# power.net
KiCad netlist of a schematic drawn in Altium Designer
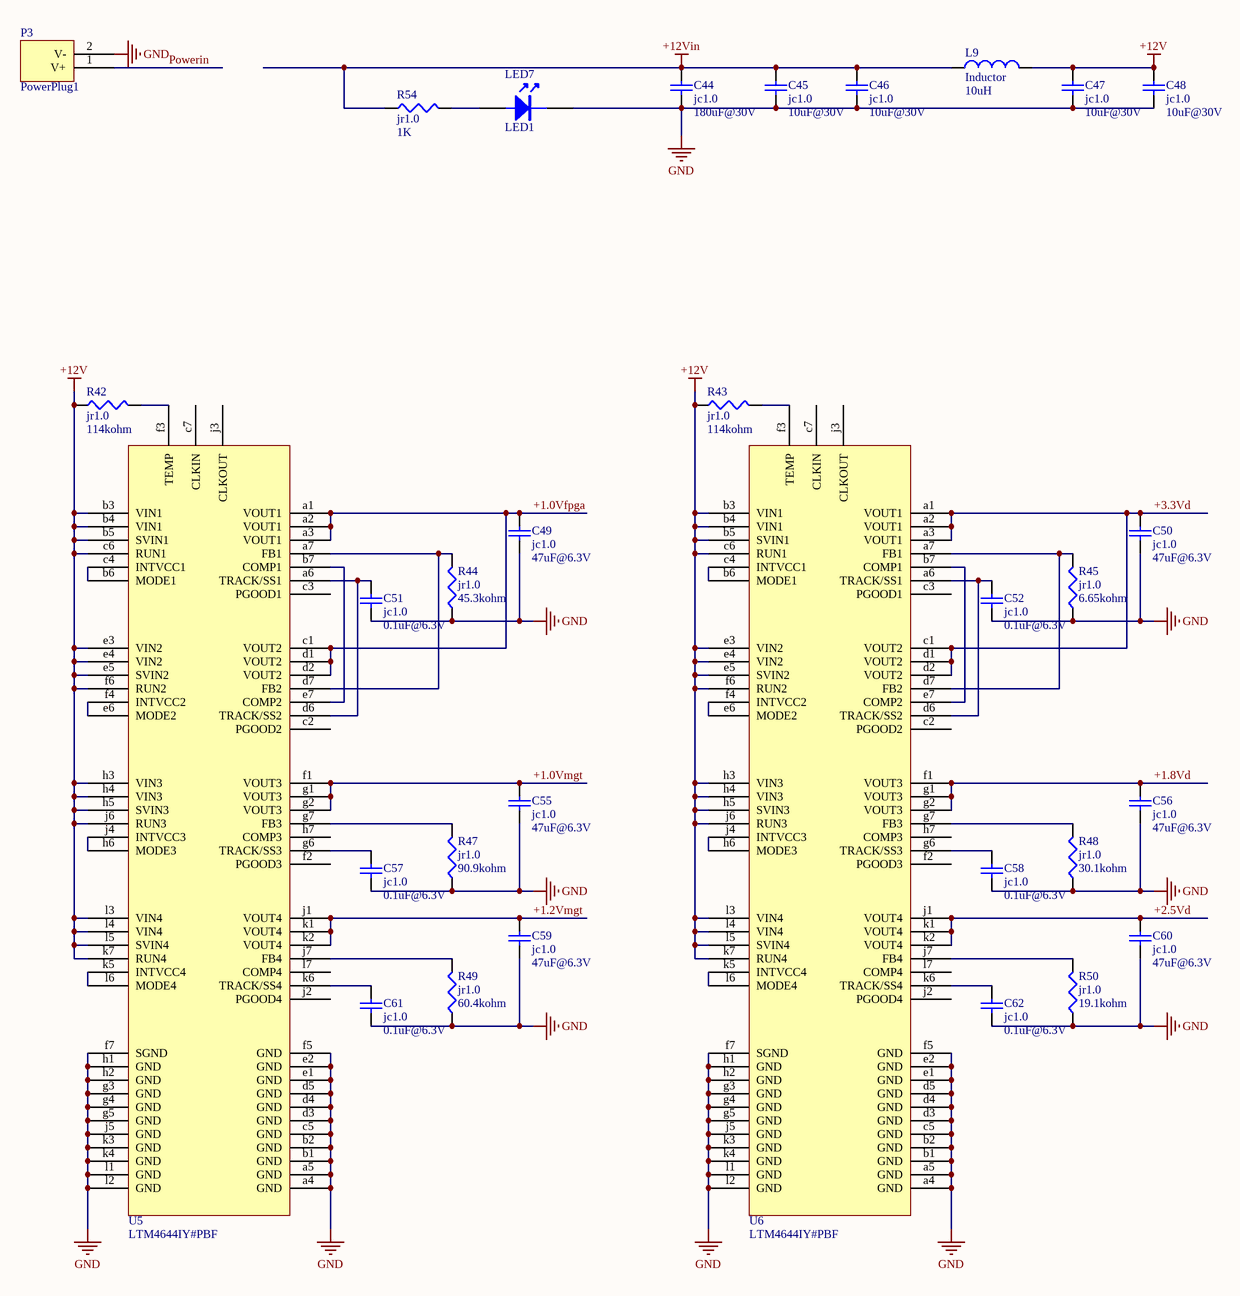
[diagram p0: power.SchDoc]

(export (version "E")
  (design (tool "Eeschema 10.0.6"))
  (components
    (comp (ref "C44")
      (value "jc1.0")
      (footprint "2220")
      (description "Capacitor")
      (fields (field (name "ALTIUM_VALUE") "180uF@30V") (field (name "PUBLISHER") "Altium Limited"))
      (libsource (lib "LIB01DXP2006SchLib") (part "Cap"))
    )
    (comp (ref "C45")
      (value "jc1.0")
      (footprint "2220")
      (description "Capacitor")
      (fields (field (name "ALTIUM_VALUE") "10uF@30V") (field (name "PUBLISHER") "Altium Limited"))
      (libsource (lib "LIB01DXP2006SchLib") (part "Cap"))
    )
    (comp (ref "C46")
      (value "jc1.0")
      (footprint "2220")
      (description "Capacitor")
      (fields (field (name "ALTIUM_VALUE") "10uF@30V") (field (name "PUBLISHER") "Altium Limited"))
      (libsource (lib "LIB01DXP2006SchLib") (part "Cap"))
    )
    (comp (ref "C47")
      (value "jc1.0")
      (footprint "2220")
      (description "Capacitor")
      (fields (field (name "ALTIUM_VALUE") "10uF@30V") (field (name "PUBLISHER") "Altium Limited"))
      (libsource (lib "LIB01DXP2006SchLib") (part "Cap"))
    )
    (comp (ref "C48")
      (value "jc1.0")
      (footprint "2220")
      (description "Capacitor")
      (fields (field (name "ALTIUM_VALUE") "10uF@30V") (field (name "PUBLISHER") "Altium Limited"))
      (libsource (lib "LIB01DXP2006SchLib") (part "Cap"))
    )
    (comp (ref "C49")
      (value "jc1.0")
      (footprint "0805")
      (description "Capacitor")
      (fields (field (name "ALTIUM_VALUE") "47uF@6.3V") (field (name "PUBLISHER") "Altium Limited"))
      (libsource (lib "LIB01DXP2006SchLib") (part "Cap"))
    )
    (comp (ref "C50")
      (value "jc1.0")
      (footprint "0805")
      (description "Capacitor")
      (fields (field (name "ALTIUM_VALUE") "47uF@6.3V") (field (name "PUBLISHER") "Altium Limited"))
      (libsource (lib "LIB01DXP2006SchLib") (part "Cap"))
    )
    (comp (ref "C51")
      (value "jc1.0")
      (footprint "0402")
      (description "Capacitor")
      (fields (field (name "ALTIUM_VALUE") "0.1uF@6.3V") (field (name "PUBLISHER") "Altium Limited"))
      (libsource (lib "LIB01DXP2006SchLib") (part "Cap"))
    )
    (comp (ref "C52")
      (value "jc1.0")
      (footprint "0402")
      (description "Capacitor")
      (fields (field (name "ALTIUM_VALUE") "0.1uF@6.3V") (field (name "PUBLISHER") "Altium Limited"))
      (libsource (lib "LIB01DXP2006SchLib") (part "Cap"))
    )
    (comp (ref "C55")
      (value "jc1.0")
      (footprint "0805")
      (description "Capacitor")
      (fields (field (name "ALTIUM_VALUE") "47uF@6.3V") (field (name "PUBLISHER") "Altium Limited"))
      (libsource (lib "LIB01DXP2006SchLib") (part "Cap"))
    )
    (comp (ref "C56")
      (value "jc1.0")
      (footprint "0805")
      (description "Capacitor")
      (fields (field (name "ALTIUM_VALUE") "47uF@6.3V") (field (name "PUBLISHER") "Altium Limited"))
      (libsource (lib "LIB01DXP2006SchLib") (part "Cap"))
    )
    (comp (ref "C57")
      (value "jc1.0")
      (footprint "0402")
      (description "Capacitor")
      (fields (field (name "ALTIUM_VALUE") "0.1uF@6.3V") (field (name "PUBLISHER") "Altium Limited"))
      (libsource (lib "LIB01DXP2006SchLib") (part "Cap"))
    )
    (comp (ref "C58")
      (value "jc1.0")
      (footprint "0402")
      (description "Capacitor")
      (fields (field (name "ALTIUM_VALUE") "0.1uF@6.3V") (field (name "PUBLISHER") "Altium Limited"))
      (libsource (lib "LIB01DXP2006SchLib") (part "Cap"))
    )
    (comp (ref "C59")
      (value "jc1.0")
      (footprint "0805")
      (description "Capacitor")
      (fields (field (name "ALTIUM_VALUE") "47uF@6.3V") (field (name "PUBLISHER") "Altium Limited"))
      (libsource (lib "LIB01DXP2006SchLib") (part "Cap"))
    )
    (comp (ref "C60")
      (value "jc1.0")
      (footprint "0805")
      (description "Capacitor")
      (fields (field (name "ALTIUM_VALUE") "47uF@6.3V") (field (name "PUBLISHER") "Altium Limited"))
      (libsource (lib "LIB01DXP2006SchLib") (part "Cap"))
    )
    (comp (ref "C61")
      (value "jc1.0")
      (footprint "0402")
      (description "Capacitor")
      (fields (field (name "ALTIUM_VALUE") "0.1uF@6.3V") (field (name "PUBLISHER") "Altium Limited"))
      (libsource (lib "LIB01DXP2006SchLib") (part "Cap"))
    )
    (comp (ref "C62")
      (value "jc1.0")
      (footprint "0402")
      (description "Capacitor")
      (fields (field (name "ALTIUM_VALUE") "0.1uF@6.3V") (field (name "PUBLISHER") "Altium Limited"))
      (libsource (lib "LIB01DXP2006SchLib") (part "Cap"))
    )
    (comp (ref "L9")
      (value "Inductor")
      (footprint "AXIAL0.3 - 35")
      (fields (field (name "ALTIUM_VALUE") "10uH") (field (name "PUBLISHER") "Altium Limited"))
      (libsource (lib "LIB01DXP2006SchLib") (part "Inductor"))
    )
    (comp (ref "LED7") (value "LED1") (footprint "LED1") (libsource (lib "LIB01DXP2006SchLib") (part "LED1")))
    (comp (ref "P3")
      (value "PowerPlug1")
      (footprint "POWERPLUG1")
      (libsource (lib "LIB01DXP2006SchLib") (part "PowerPlug1"))
    )
    (comp (ref "R42")
      (value "jr1.0")
      (footprint "0402")
      (description "Resistor")
      (fields (field (name "ALTIUM_VALUE") "114kohm") (field (name "PUBLISHER") "Altium Limited"))
      (libsource (lib "LIB01DXP2006SchLib") (part "Res"))
    )
    (comp (ref "R43")
      (value "jr1.0")
      (footprint "0402")
      (description "Resistor")
      (fields (field (name "ALTIUM_VALUE") "114kohm") (field (name "PUBLISHER") "Altium Limited"))
      (libsource (lib "LIB01DXP2006SchLib") (part "Res"))
    )
    (comp (ref "R44")
      (value "jr1.0")
      (footprint "0805")
      (description "Resistor")
      (fields (field (name "ALTIUM_VALUE") "45.3kohm") (field (name "PUBLISHER") "Altium Limited"))
      (libsource (lib "LIB01DXP2006SchLib") (part "Res"))
    )
    (comp (ref "R45")
      (value "jr1.0")
      (footprint "0805")
      (description "Resistor")
      (fields (field (name "ALTIUM_VALUE") "6.65kohm") (field (name "PUBLISHER") "Altium Limited"))
      (libsource (lib "LIB01DXP2006SchLib") (part "Res"))
    )
    (comp (ref "R47")
      (value "jr1.0")
      (footprint "0805")
      (description "Resistor")
      (fields (field (name "ALTIUM_VALUE") "90.9kohm") (field (name "PUBLISHER") "Altium Limited"))
      (libsource (lib "LIB01DXP2006SchLib") (part "Res"))
    )
    (comp (ref "R48")
      (value "jr1.0")
      (footprint "0805")
      (description "Resistor")
      (fields (field (name "ALTIUM_VALUE") "30.1kohm") (field (name "PUBLISHER") "Altium Limited"))
      (libsource (lib "LIB01DXP2006SchLib") (part "Res"))
    )
    (comp (ref "R49")
      (value "jr1.0")
      (footprint "0805")
      (description "Resistor")
      (fields (field (name "ALTIUM_VALUE") "60.4kohm") (field (name "PUBLISHER") "Altium Limited"))
      (libsource (lib "LIB01DXP2006SchLib") (part "Res"))
    )
    (comp (ref "R50")
      (value "jr1.0")
      (footprint "0805")
      (description "Resistor")
      (fields (field (name "ALTIUM_VALUE") "19.1kohm") (field (name "PUBLISHER") "Altium Limited"))
      (libsource (lib "LIB01DXP2006SchLib") (part "Res"))
    )
    (comp (ref "R54")
      (value "jr1.0")
      (footprint "0805")
      (description "Resistor")
      (fields (field (name "ALTIUM_VALUE") "1K") (field (name "PUBLISHER") "Altium Limited"))
      (libsource (lib "LIB01DXP2006SchLib") (part "Res"))
    )
    (comp (ref "U5")
      (value "LTM4644IY#PBF")
      (footprint "BGA77C127P7X11_900X1500X521")
      (libsource (lib "LIB01DXP2006SchLib") (part "LTM4644IY#PBF"))
    )
    (comp (ref "U6")
      (value "LTM4644IY#PBF")
      (footprint "BGA77C127P7X11_900X1500X521")
      (libsource (lib "LIB01DXP2006SchLib") (part "LTM4644IY#PBF"))
    )
  )
  (nets
    (net (code "1") (name "+12V") (class "Default")
      (node (ref "C47") (pin "2") (pinfunction "2_2") (pintype "passive"))
      (node (ref "C48") (pin "2") (pinfunction "2_2") (pintype "passive"))
      (node (ref "L9") (pin "2") (pinfunction "2_2") (pintype "passive"))
      (node (ref "R42") (pin "1") (pinfunction "1_1") (pintype "passive"))
      (node (ref "R43") (pin "1") (pinfunction "1_1") (pintype "passive"))
      (node (ref "U5") (pin "b3") (pinfunction "VIN1_b3") (pintype "passive"))
      (node (ref "U5") (pin "b4") (pinfunction "VIN1_b4") (pintype "passive"))
      (node (ref "U5") (pin "b5") (pinfunction "SVIN1_b5") (pintype "passive"))
      (node (ref "U5") (pin "c6") (pinfunction "RUN1_c6") (pintype "passive"))
      (node (ref "U5") (pin "e3") (pinfunction "VIN2_e3") (pintype "passive"))
      (node (ref "U5") (pin "e4") (pinfunction "VIN2_e4") (pintype "passive"))
      (node (ref "U5") (pin "e5") (pinfunction "SVIN2_e5") (pintype "passive"))
      (node (ref "U5") (pin "f6") (pinfunction "RUN2_f6") (pintype "passive"))
      (node (ref "U5") (pin "h3") (pinfunction "VIN3_h3") (pintype "passive"))
      (node (ref "U5") (pin "h4") (pinfunction "VIN3_h4") (pintype "passive"))
      (node (ref "U5") (pin "h5") (pinfunction "SVIN3_h5") (pintype "passive"))
      (node (ref "U5") (pin "j6") (pinfunction "RUN3_j6") (pintype "passive"))
      (node (ref "U5") (pin "k7") (pinfunction "RUN4_k7") (pintype "passive"))
      (node (ref "U5") (pin "l3") (pinfunction "VIN4_l3") (pintype "passive"))
      (node (ref "U5") (pin "l4") (pinfunction "VIN4_l4") (pintype "passive"))
      (node (ref "U5") (pin "l5") (pinfunction "SVIN4_l5") (pintype "passive"))
      (node (ref "U6") (pin "b3") (pinfunction "VIN1_b3") (pintype "passive"))
      (node (ref "U6") (pin "b4") (pinfunction "VIN1_b4") (pintype "passive"))
      (node (ref "U6") (pin "b5") (pinfunction "SVIN1_b5") (pintype "passive"))
      (node (ref "U6") (pin "c6") (pinfunction "RUN1_c6") (pintype "passive"))
      (node (ref "U6") (pin "e3") (pinfunction "VIN2_e3") (pintype "passive"))
      (node (ref "U6") (pin "e4") (pinfunction "VIN2_e4") (pintype "passive"))
      (node (ref "U6") (pin "e5") (pinfunction "SVIN2_e5") (pintype "passive"))
      (node (ref "U6") (pin "f6") (pinfunction "RUN2_f6") (pintype "passive"))
      (node (ref "U6") (pin "h3") (pinfunction "VIN3_h3") (pintype "passive"))
      (node (ref "U6") (pin "h4") (pinfunction "VIN3_h4") (pintype "passive"))
      (node (ref "U6") (pin "h5") (pinfunction "SVIN3_h5") (pintype "passive"))
      (node (ref "U6") (pin "j6") (pinfunction "RUN3_j6") (pintype "passive"))
      (node (ref "U6") (pin "k7") (pinfunction "RUN4_k7") (pintype "passive"))
      (node (ref "U6") (pin "l3") (pinfunction "VIN4_l3") (pintype "passive"))
      (node (ref "U6") (pin "l4") (pinfunction "VIN4_l4") (pintype "passive"))
      (node (ref "U6") (pin "l5") (pinfunction "SVIN4_l5") (pintype "passive"))
    )
    (net (code "2") (name "+12Vin") (class "Default")
      (node (ref "C44") (pin "2") (pinfunction "2_2") (pintype "passive"))
      (node (ref "C45") (pin "2") (pinfunction "2_2") (pintype "passive"))
      (node (ref "C46") (pin "2") (pinfunction "2_2") (pintype "passive"))
      (node (ref "L9") (pin "1") (pinfunction "1_1") (pintype "passive"))
      (node (ref "R54") (pin "1") (pinfunction "1_1") (pintype "passive"))
    )
    (net (code "3") (name "/+1.0Vfpga") (class "Default")
      (node (ref "C49") (pin "2") (pinfunction "2_2") (pintype "passive"))
      (node (ref "U5") (pin "a1") (pinfunction "VOUT1_a1") (pintype "passive"))
      (node (ref "U5") (pin "a2") (pinfunction "VOUT1_a2") (pintype "passive"))
      (node (ref "U5") (pin "a3") (pinfunction "VOUT1_a3") (pintype "passive"))
      (node (ref "U5") (pin "c1") (pinfunction "VOUT2_c1") (pintype "passive"))
      (node (ref "U5") (pin "d1") (pinfunction "VOUT2_d1") (pintype "passive"))
      (node (ref "U5") (pin "d2") (pinfunction "VOUT2_d2") (pintype "passive"))
    )
    (net (code "4") (name "/+1.0Vmgt") (class "Default")
      (node (ref "C55") (pin "2") (pinfunction "2_2") (pintype "passive"))
      (node (ref "U5") (pin "f1") (pinfunction "VOUT3_f1") (pintype "passive"))
      (node (ref "U5") (pin "g1") (pinfunction "VOUT3_g1") (pintype "passive"))
      (node (ref "U5") (pin "g2") (pinfunction "VOUT3_g2") (pintype "passive"))
    )
    (net (code "5") (name "/+1.2Vmgt") (class "Default")
      (node (ref "C59") (pin "2") (pinfunction "2_2") (pintype "passive"))
      (node (ref "U5") (pin "j1") (pinfunction "VOUT4_j1") (pintype "passive"))
      (node (ref "U5") (pin "k1") (pinfunction "VOUT4_k1") (pintype "passive"))
      (node (ref "U5") (pin "k2") (pinfunction "VOUT4_k2") (pintype "passive"))
    )
    (net (code "6") (name "/+1.8Vd") (class "Default")
      (node (ref "C56") (pin "2") (pinfunction "2_2") (pintype "passive"))
      (node (ref "U6") (pin "f1") (pinfunction "VOUT3_f1") (pintype "passive"))
      (node (ref "U6") (pin "g1") (pinfunction "VOUT3_g1") (pintype "passive"))
      (node (ref "U6") (pin "g2") (pinfunction "VOUT3_g2") (pintype "passive"))
    )
    (net (code "7") (name "/+2.5Vd") (class "Default")
      (node (ref "C60") (pin "2") (pinfunction "2_2") (pintype "passive"))
      (node (ref "U6") (pin "j1") (pinfunction "VOUT4_j1") (pintype "passive"))
      (node (ref "U6") (pin "k1") (pinfunction "VOUT4_k1") (pintype "passive"))
      (node (ref "U6") (pin "k2") (pinfunction "VOUT4_k2") (pintype "passive"))
    )
    (net (code "8") (name "/+3.3Vd") (class "Default")
      (node (ref "C50") (pin "2") (pinfunction "2_2") (pintype "passive"))
      (node (ref "U6") (pin "a1") (pinfunction "VOUT1_a1") (pintype "passive"))
      (node (ref "U6") (pin "a2") (pinfunction "VOUT1_a2") (pintype "passive"))
      (node (ref "U6") (pin "a3") (pinfunction "VOUT1_a3") (pintype "passive"))
      (node (ref "U6") (pin "c1") (pinfunction "VOUT2_c1") (pintype "passive"))
      (node (ref "U6") (pin "d1") (pinfunction "VOUT2_d1") (pintype "passive"))
      (node (ref "U6") (pin "d2") (pinfunction "VOUT2_d2") (pintype "passive"))
    )
    (net (code "9") (name "/Powerin") (class "Default")
      (node (ref "P3") (pin "1") (pinfunction "V+_1") (pintype "passive"))
    )
    (net (code "10") (name "GND") (class "Default")
      (node (ref "C44") (pin "1") (pinfunction "1_1") (pintype "passive"))
      (node (ref "C45") (pin "1") (pinfunction "1_1") (pintype "passive"))
      (node (ref "C46") (pin "1") (pinfunction "1_1") (pintype "passive"))
      (node (ref "C47") (pin "1") (pinfunction "1_1") (pintype "passive"))
      (node (ref "C48") (pin "1") (pinfunction "1_1") (pintype "passive"))
      (node (ref "C49") (pin "1") (pinfunction "1_1") (pintype "passive"))
      (node (ref "C50") (pin "1") (pinfunction "1_1") (pintype "passive"))
      (node (ref "C51") (pin "1") (pinfunction "1_1") (pintype "passive"))
      (node (ref "C52") (pin "1") (pinfunction "1_1") (pintype "passive"))
      (node (ref "C55") (pin "1") (pinfunction "1_1") (pintype "passive"))
      (node (ref "C56") (pin "1") (pinfunction "1_1") (pintype "passive"))
      (node (ref "C57") (pin "1") (pinfunction "1_1") (pintype "passive"))
      (node (ref "C58") (pin "1") (pinfunction "1_1") (pintype "passive"))
      (node (ref "C59") (pin "1") (pinfunction "1_1") (pintype "passive"))
      (node (ref "C60") (pin "1") (pinfunction "1_1") (pintype "passive"))
      (node (ref "C61") (pin "1") (pinfunction "1_1") (pintype "passive"))
      (node (ref "C62") (pin "1") (pinfunction "1_1") (pintype "passive"))
      (node (ref "LED7") (pin "2") (pinfunction "2_2") (pintype "passive"))
      (node (ref "P3") (pin "2") (pinfunction "V-_2") (pintype "passive"))
      (node (ref "R44") (pin "1") (pinfunction "1_1") (pintype "passive"))
      (node (ref "R45") (pin "1") (pinfunction "1_1") (pintype "passive"))
      (node (ref "R47") (pin "1") (pinfunction "1_1") (pintype "passive"))
      (node (ref "R48") (pin "1") (pinfunction "1_1") (pintype "passive"))
      (node (ref "R49") (pin "1") (pinfunction "1_1") (pintype "passive"))
      (node (ref "R50") (pin "1") (pinfunction "1_1") (pintype "passive"))
      (node (ref "U5") (pin "a4") (pinfunction "GND_a4") (pintype "passive"))
      (node (ref "U5") (pin "a5") (pinfunction "GND_a5") (pintype "passive"))
      (node (ref "U5") (pin "b1") (pinfunction "GND_b1") (pintype "passive"))
      (node (ref "U5") (pin "b2") (pinfunction "GND_b2") (pintype "passive"))
      (node (ref "U5") (pin "c5") (pinfunction "GND_c5") (pintype "passive"))
      (node (ref "U5") (pin "d3") (pinfunction "GND_d3") (pintype "passive"))
      (node (ref "U5") (pin "d4") (pinfunction "GND_d4") (pintype "passive"))
      (node (ref "U5") (pin "d5") (pinfunction "GND_d5") (pintype "passive"))
      (node (ref "U5") (pin "e1") (pinfunction "GND_e1") (pintype "passive"))
      (node (ref "U5") (pin "e2") (pinfunction "GND_e2") (pintype "passive"))
      (node (ref "U5") (pin "f5") (pinfunction "GND_f5") (pintype "passive"))
      (node (ref "U5") (pin "f7") (pinfunction "SGND_f7") (pintype "passive"))
      (node (ref "U5") (pin "g3") (pinfunction "GND_g3") (pintype "passive"))
      (node (ref "U5") (pin "g4") (pinfunction "GND_g4") (pintype "passive"))
      (node (ref "U5") (pin "g5") (pinfunction "GND_g5") (pintype "passive"))
      (node (ref "U5") (pin "h1") (pinfunction "GND_h1") (pintype "passive"))
      (node (ref "U5") (pin "h2") (pinfunction "GND_h2") (pintype "passive"))
      (node (ref "U5") (pin "j5") (pinfunction "GND_j5") (pintype "passive"))
      (node (ref "U5") (pin "k3") (pinfunction "GND_k3") (pintype "passive"))
      (node (ref "U5") (pin "k4") (pinfunction "GND_k4") (pintype "passive"))
      (node (ref "U5") (pin "l1") (pinfunction "GND_l1") (pintype "passive"))
      (node (ref "U5") (pin "l2") (pinfunction "GND_l2") (pintype "passive"))
      (node (ref "U6") (pin "a4") (pinfunction "GND_a4") (pintype "passive"))
      (node (ref "U6") (pin "a5") (pinfunction "GND_a5") (pintype "passive"))
      (node (ref "U6") (pin "b1") (pinfunction "GND_b1") (pintype "passive"))
      (node (ref "U6") (pin "b2") (pinfunction "GND_b2") (pintype "passive"))
      (node (ref "U6") (pin "c5") (pinfunction "GND_c5") (pintype "passive"))
      (node (ref "U6") (pin "d3") (pinfunction "GND_d3") (pintype "passive"))
      (node (ref "U6") (pin "d4") (pinfunction "GND_d4") (pintype "passive"))
      (node (ref "U6") (pin "d5") (pinfunction "GND_d5") (pintype "passive"))
      (node (ref "U6") (pin "e1") (pinfunction "GND_e1") (pintype "passive"))
      (node (ref "U6") (pin "e2") (pinfunction "GND_e2") (pintype "passive"))
      (node (ref "U6") (pin "f5") (pinfunction "GND_f5") (pintype "passive"))
      (node (ref "U6") (pin "f7") (pinfunction "SGND_f7") (pintype "passive"))
      (node (ref "U6") (pin "g3") (pinfunction "GND_g3") (pintype "passive"))
      (node (ref "U6") (pin "g4") (pinfunction "GND_g4") (pintype "passive"))
      (node (ref "U6") (pin "g5") (pinfunction "GND_g5") (pintype "passive"))
      (node (ref "U6") (pin "h1") (pinfunction "GND_h1") (pintype "passive"))
      (node (ref "U6") (pin "h2") (pinfunction "GND_h2") (pintype "passive"))
      (node (ref "U6") (pin "j5") (pinfunction "GND_j5") (pintype "passive"))
      (node (ref "U6") (pin "k3") (pinfunction "GND_k3") (pintype "passive"))
      (node (ref "U6") (pin "k4") (pinfunction "GND_k4") (pintype "passive"))
      (node (ref "U6") (pin "l1") (pinfunction "GND_l1") (pintype "passive"))
      (node (ref "U6") (pin "l2") (pinfunction "GND_l2") (pintype "passive"))
    )
    (net (code "11") (name "Net-(LED7-Pad1)") (class "Default")
      (node (ref "LED7") (pin "1") (pinfunction "1_1") (pintype "passive"))
      (node (ref "R54") (pin "2") (pinfunction "2_2") (pintype "passive"))
    )
    (net (code "12") (name "Net-(U5-COMP1)") (class "Default")
      (node (ref "U5") (pin "b7") (pinfunction "COMP1_b7") (pintype "passive"))
      (node (ref "U5") (pin "e7") (pinfunction "COMP2_e7") (pintype "passive"))
    )
    (net (code "13") (name "Net-(U5-FB1)") (class "Default")
      (node (ref "R44") (pin "2") (pinfunction "2_2") (pintype "passive"))
      (node (ref "U5") (pin "a7") (pinfunction "FB1_a7") (pintype "passive"))
      (node (ref "U5") (pin "d7") (pinfunction "FB2_d7") (pintype "passive"))
    )
    (net (code "14") (name "Net-(U5-FB3)") (class "Default")
      (node (ref "R47") (pin "2") (pinfunction "2_2") (pintype "passive"))
      (node (ref "U5") (pin "g7") (pinfunction "FB3_g7") (pintype "passive"))
    )
    (net (code "15") (name "Net-(U5-FB4)") (class "Default")
      (node (ref "R49") (pin "2") (pinfunction "2_2") (pintype "passive"))
      (node (ref "U5") (pin "j7") (pinfunction "FB4_j7") (pintype "passive"))
    )
    (net (code "16") (name "Net-(U5-INTVCC1)") (class "Default")
      (node (ref "U5") (pin "b6") (pinfunction "MODE1_b6") (pintype "passive"))
      (node (ref "U5") (pin "c4") (pinfunction "INTVCC1_c4") (pintype "passive"))
    )
    (net (code "17") (name "Net-(U5-INTVCC2)") (class "Default")
      (node (ref "U5") (pin "e6") (pinfunction "MODE2_e6") (pintype "passive"))
      (node (ref "U5") (pin "f4") (pinfunction "INTVCC2_f4") (pintype "passive"))
    )
    (net (code "18") (name "Net-(U5-INTVCC3)") (class "Default")
      (node (ref "U5") (pin "h6") (pinfunction "MODE3_h6") (pintype "passive"))
      (node (ref "U5") (pin "j4") (pinfunction "INTVCC3_j4") (pintype "passive"))
    )
    (net (code "19") (name "Net-(U5-INTVCC4)") (class "Default")
      (node (ref "U5") (pin "k5") (pinfunction "INTVCC4_k5") (pintype "passive"))
      (node (ref "U5") (pin "l6") (pinfunction "MODE4_l6") (pintype "passive"))
    )
    (net (code "20") (name "Net-(U5-TEMP)") (class "Default")
      (node (ref "R42") (pin "2") (pinfunction "2_2") (pintype "passive"))
      (node (ref "U5") (pin "f3") (pinfunction "TEMP_f3") (pintype "passive"))
    )
    (net (code "21") (name "Net-(U5-TRACK{slash}SS1)") (class "Default")
      (node (ref "C51") (pin "2") (pinfunction "2_2") (pintype "passive"))
      (node (ref "U5") (pin "a6") (pinfunction "TRACK/SS1_a6") (pintype "passive"))
      (node (ref "U5") (pin "d6") (pinfunction "TRACK/SS2_d6") (pintype "passive"))
    )
    (net (code "22") (name "Net-(U5-TRACK{slash}SS3)") (class "Default")
      (node (ref "C57") (pin "2") (pinfunction "2_2") (pintype "passive"))
      (node (ref "U5") (pin "g6") (pinfunction "TRACK/SS3_g6") (pintype "passive"))
    )
    (net (code "23") (name "Net-(U5-TRACK{slash}SS4)") (class "Default")
      (node (ref "C61") (pin "2") (pinfunction "2_2") (pintype "passive"))
      (node (ref "U5") (pin "k6") (pinfunction "TRACK/SS4_k6") (pintype "passive"))
    )
    (net (code "24") (name "Net-(U6-COMP1)") (class "Default")
      (node (ref "U6") (pin "b7") (pinfunction "COMP1_b7") (pintype "passive"))
      (node (ref "U6") (pin "e7") (pinfunction "COMP2_e7") (pintype "passive"))
    )
    (net (code "25") (name "Net-(U6-FB1)") (class "Default")
      (node (ref "R45") (pin "2") (pinfunction "2_2") (pintype "passive"))
      (node (ref "U6") (pin "a7") (pinfunction "FB1_a7") (pintype "passive"))
      (node (ref "U6") (pin "d7") (pinfunction "FB2_d7") (pintype "passive"))
    )
    (net (code "26") (name "Net-(U6-FB3)") (class "Default")
      (node (ref "R48") (pin "2") (pinfunction "2_2") (pintype "passive"))
      (node (ref "U6") (pin "g7") (pinfunction "FB3_g7") (pintype "passive"))
    )
    (net (code "27") (name "Net-(U6-FB4)") (class "Default")
      (node (ref "R50") (pin "2") (pinfunction "2_2") (pintype "passive"))
      (node (ref "U6") (pin "j7") (pinfunction "FB4_j7") (pintype "passive"))
    )
    (net (code "28") (name "Net-(U6-INTVCC1)") (class "Default")
      (node (ref "U6") (pin "b6") (pinfunction "MODE1_b6") (pintype "passive"))
      (node (ref "U6") (pin "c4") (pinfunction "INTVCC1_c4") (pintype "passive"))
    )
    (net (code "29") (name "Net-(U6-INTVCC2)") (class "Default")
      (node (ref "U6") (pin "e6") (pinfunction "MODE2_e6") (pintype "passive"))
      (node (ref "U6") (pin "f4") (pinfunction "INTVCC2_f4") (pintype "passive"))
    )
    (net (code "30") (name "Net-(U6-INTVCC3)") (class "Default")
      (node (ref "U6") (pin "h6") (pinfunction "MODE3_h6") (pintype "passive"))
      (node (ref "U6") (pin "j4") (pinfunction "INTVCC3_j4") (pintype "passive"))
    )
    (net (code "31") (name "Net-(U6-INTVCC4)") (class "Default")
      (node (ref "U6") (pin "k5") (pinfunction "INTVCC4_k5") (pintype "passive"))
      (node (ref "U6") (pin "l6") (pinfunction "MODE4_l6") (pintype "passive"))
    )
    (net (code "32") (name "Net-(U6-TEMP)") (class "Default")
      (node (ref "R43") (pin "2") (pinfunction "2_2") (pintype "passive"))
      (node (ref "U6") (pin "f3") (pinfunction "TEMP_f3") (pintype "passive"))
    )
    (net (code "33") (name "Net-(U6-TRACK{slash}SS1)") (class "Default")
      (node (ref "C52") (pin "2") (pinfunction "2_2") (pintype "passive"))
      (node (ref "U6") (pin "a6") (pinfunction "TRACK/SS1_a6") (pintype "passive"))
      (node (ref "U6") (pin "d6") (pinfunction "TRACK/SS2_d6") (pintype "passive"))
    )
    (net (code "34") (name "Net-(U6-TRACK{slash}SS3)") (class "Default")
      (node (ref "C58") (pin "2") (pinfunction "2_2") (pintype "passive"))
      (node (ref "U6") (pin "g6") (pinfunction "TRACK/SS3_g6") (pintype "passive"))
    )
    (net (code "35") (name "Net-(U6-TRACK{slash}SS4)") (class "Default")
      (node (ref "C62") (pin "2") (pinfunction "2_2") (pintype "passive"))
      (node (ref "U6") (pin "k6") (pinfunction "TRACK/SS4_k6") (pintype "passive"))
    )
    (net (code "36") (name "unconnected-(U5-CLKIN-Padc7)") (class "Default")
      (node (ref "U5") (pin "c7") (pinfunction "CLKIN_c7") (pintype "passive"))
    )
    (net (code "37") (name "unconnected-(U5-CLKOUT-Padj3)") (class "Default")
      (node (ref "U5") (pin "j3") (pinfunction "CLKOUT_j3") (pintype "passive"))
    )
    (net (code "38") (name "unconnected-(U5-COMP3-Padh7)") (class "Default")
      (node (ref "U5") (pin "h7") (pinfunction "COMP3_h7") (pintype "passive"))
    )
    (net (code "39") (name "unconnected-(U5-COMP4-Padl7)") (class "Default")
      (node (ref "U5") (pin "l7") (pinfunction "COMP4_l7") (pintype "passive"))
    )
    (net (code "40") (name "unconnected-(U5-PGOOD1-Padc3)") (class "Default")
      (node (ref "U5") (pin "c3") (pinfunction "PGOOD1_c3") (pintype "passive"))
    )
    (net (code "41") (name "unconnected-(U5-PGOOD2-Padc2)") (class "Default")
      (node (ref "U5") (pin "c2") (pinfunction "PGOOD2_c2") (pintype "passive"))
    )
    (net (code "42") (name "unconnected-(U5-PGOOD3-Padf2)") (class "Default")
      (node (ref "U5") (pin "f2") (pinfunction "PGOOD3_f2") (pintype "passive"))
    )
    (net (code "43") (name "unconnected-(U5-PGOOD4-Padj2)") (class "Default")
      (node (ref "U5") (pin "j2") (pinfunction "PGOOD4_j2") (pintype "passive"))
    )
    (net (code "44") (name "unconnected-(U6-CLKIN-Padc7)") (class "Default")
      (node (ref "U6") (pin "c7") (pinfunction "CLKIN_c7") (pintype "passive"))
    )
    (net (code "45") (name "unconnected-(U6-CLKOUT-Padj3)") (class "Default")
      (node (ref "U6") (pin "j3") (pinfunction "CLKOUT_j3") (pintype "passive"))
    )
    (net (code "46") (name "unconnected-(U6-COMP3-Padh7)") (class "Default")
      (node (ref "U6") (pin "h7") (pinfunction "COMP3_h7") (pintype "passive"))
    )
    (net (code "47") (name "unconnected-(U6-COMP4-Padl7)") (class "Default")
      (node (ref "U6") (pin "l7") (pinfunction "COMP4_l7") (pintype "passive"))
    )
    (net (code "48") (name "unconnected-(U6-PGOOD1-Padc3)") (class "Default")
      (node (ref "U6") (pin "c3") (pinfunction "PGOOD1_c3") (pintype "passive"))
    )
    (net (code "49") (name "unconnected-(U6-PGOOD2-Padc2)") (class "Default")
      (node (ref "U6") (pin "c2") (pinfunction "PGOOD2_c2") (pintype "passive"))
    )
    (net (code "50") (name "unconnected-(U6-PGOOD3-Padf2)") (class "Default")
      (node (ref "U6") (pin "f2") (pinfunction "PGOOD3_f2") (pintype "passive"))
    )
    (net (code "51") (name "unconnected-(U6-PGOOD4-Padj2)") (class "Default")
      (node (ref "U6") (pin "j2") (pinfunction "PGOOD4_j2") (pintype "passive"))
    )
  )
)
